# i2c_devices.net
KiCad netlist of a schematic drawn in Altium Designer
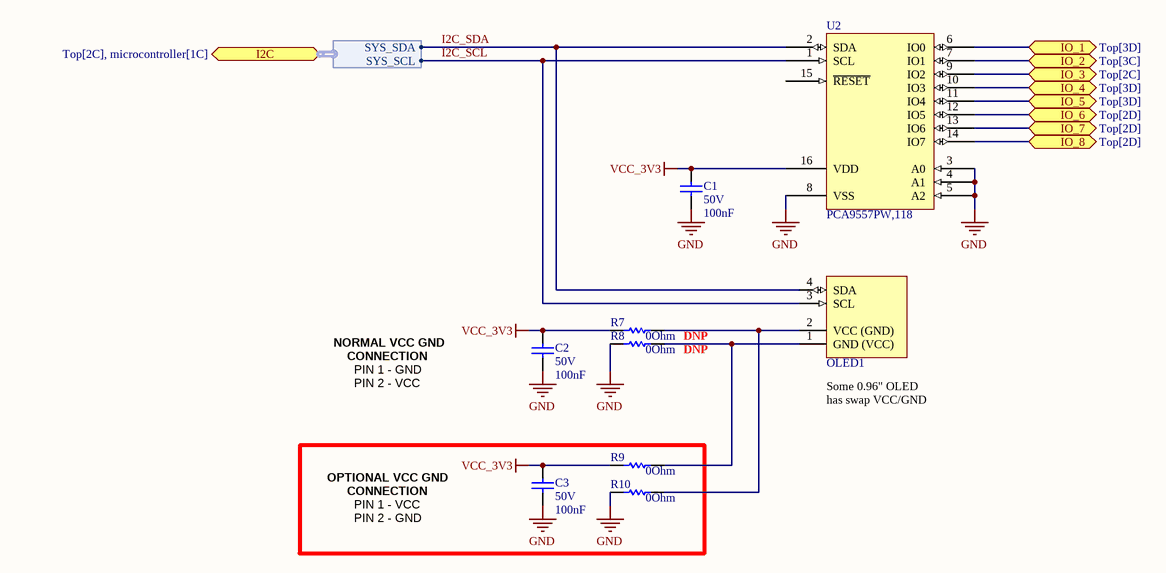
[diagram p0: i2c_devices.SchDoc]

(export (version "E")
  (design (tool "Eeschema 10.0.6"))
  (components
    (comp (ref "C1")
      (value "~")
      (footprint "CAP_0603_High_density")
      (description "Generic Ceramic Capacitor SMD")
      (fields
        (field (name "TOLERANCE") "10%")
        (field (name "VOLTAGE") "50V")
        (field (name "CAPACITANCE") "100nF")
      )
      (libsource (lib "altium_conclusive_library") (part "Capacitor SMD"))
    )
    (comp (ref "C2")
      (value "~")
      (footprint "CAP_0603_High_density")
      (description "Generic Ceramic Capacitor SMD")
      (fields
        (field (name "TOLERANCE") "10%")
        (field (name "VOLTAGE") "50V")
        (field (name "CAPACITANCE") "100nF")
      )
      (libsource (lib "altium_conclusive_library") (part "Capacitor SMD"))
    )
    (comp (ref "C3")
      (value "~")
      (footprint "CAP_0603_High_density")
      (description "Generic Ceramic Capacitor SMD")
      (fields
        (field (name "TOLERANCE") "10%")
        (field (name "VOLTAGE") "50V")
        (field (name "CAPACITANCE") "100nF")
      )
      (libsource (lib "altium_conclusive_library") (part "Capacitor SMD"))
    )
    (comp (ref "OLED1")
      (value "MDOB128064WV-YBI")
      (footprint "OLED_I2C")
      (description "Graphic OLED, 128 x 64 Pixels, Yellow on Black, 3.3V, I2C, 27.30mm x 27.30mm x 2.72mm panel size")
      (libsource (lib "altium_conclusive_library") (part "OLED_I2C"))
    )
    (comp (ref "R7")
      (value "RES_0_0402_1_1/16")
      (footprint "RES_0603")
      (description "Generic Resistor SMD")
      (fields (field (name "RESISTANCE") "0Ohm"))
      (libsource (lib "altium_conclusive_library") (part "Resistor SMD"))
    )
    (comp (ref "R8")
      (value "RES_0_0402_1_1/16")
      (footprint "RES_0603")
      (description "Generic Resistor SMD")
      (fields (field (name "RESISTANCE") "0Ohm"))
      (libsource (lib "altium_conclusive_library") (part "Resistor SMD"))
    )
    (comp (ref "R9")
      (value "RES_0_0402_1_1/16")
      (footprint "RES_0603")
      (description "Generic Resistor SMD")
      (fields (field (name "RESISTANCE") "0Ohm"))
      (libsource (lib "altium_conclusive_library") (part "Resistor SMD"))
    )
    (comp (ref "R10")
      (value "RES_0_0402_1_1/16")
      (footprint "RES_0603")
      (description "Generic Resistor SMD")
      (fields (field (name "RESISTANCE") "0Ohm"))
      (libsource (lib "altium_conclusive_library") (part "Resistor SMD"))
    )
    (comp (ref "U2")
      (value "PCA9557PW,118")
      (footprint "TSOP65P640X120-16M")
      (description "8-bit I2C-bus and SMBus I/O port with reset")
      (libsource (lib "MY_LIB") (part "PCA9557PW,118"))
    )
  )
  (nets
    (net (code "2") (name "/I2C_SCL") (class "Default")
      (node (ref "OLED1") (pin "3") (pinfunction "SCL_3") (pintype "input"))
      (node (ref "U2") (pin "1") (pinfunction "SCL_1") (pintype "input"))
    )
    (net (code "3") (name "/I2C_SDA") (class "Default")
      (node (ref "OLED1") (pin "4") (pinfunction "SDA_4") (pintype "bidirectional"))
      (node (ref "U2") (pin "2") (pinfunction "SDA_2") (pintype "bidirectional"))
    )
    (net (code "4") (name "/IO_1") (class "Default")
      (node (ref "U2") (pin "6") (pinfunction "IO0_6") (pintype "bidirectional"))
    )
    (net (code "5") (name "/IO_2") (class "Default")
      (node (ref "U2") (pin "7") (pinfunction "IO1_7") (pintype "bidirectional"))
    )
    (net (code "6") (name "/IO_3") (class "Default")
      (node (ref "U2") (pin "9") (pinfunction "IO2_9") (pintype "bidirectional"))
    )
    (net (code "7") (name "/IO_4") (class "Default")
      (node (ref "U2") (pin "10") (pinfunction "IO3_10") (pintype "bidirectional"))
    )
    (net (code "8") (name "/IO_5") (class "Default")
      (node (ref "U2") (pin "11") (pinfunction "IO4_11") (pintype "bidirectional"))
    )
    (net (code "9") (name "/IO_6") (class "Default")
      (node (ref "U2") (pin "12") (pinfunction "IO5_12") (pintype "bidirectional"))
    )
    (net (code "10") (name "/IO_7") (class "Default")
      (node (ref "U2") (pin "13") (pinfunction "IO6_13") (pintype "bidirectional"))
    )
    (net (code "11") (name "/IO_8") (class "Default")
      (node (ref "U2") (pin "14") (pinfunction "IO7_14") (pintype "bidirectional"))
    )
    (net (code "13") (name "GND") (class "Default")
      (node (ref "C1") (pin "2") (pinfunction "2_2") (pintype "passive"))
      (node (ref "C2") (pin "2") (pinfunction "2_2") (pintype "passive"))
      (node (ref "C3") (pin "2") (pinfunction "2_2") (pintype "passive"))
      (node (ref "R10") (pin "2") (pinfunction "2_2") (pintype "passive"))
      (node (ref "R8") (pin "2") (pinfunction "2_2") (pintype "passive"))
      (node (ref "U2") (pin "3") (pinfunction "A0_3") (pintype "input"))
      (node (ref "U2") (pin "4") (pinfunction "A1_4") (pintype "input"))
      (node (ref "U2") (pin "5") (pinfunction "A2_5") (pintype "input"))
      (node (ref "U2") (pin "8") (pinfunction "VSS_8") (pintype "power_in"))
    )
    (net (code "14") (name "Net-(OLED1-GND_(VCC))") (class "Default")
      (node (ref "OLED1") (pin "1") (pinfunction "GND_(VCC)_1") (pintype "passive"))
      (node (ref "R8") (pin "1") (pinfunction "1_1") (pintype "passive"))
      (node (ref "R9") (pin "1") (pinfunction "1_1") (pintype "passive"))
    )
    (net (code "15") (name "Net-(OLED1-VCC_(GND))") (class "Default")
      (node (ref "OLED1") (pin "2") (pinfunction "VCC_(GND)_2") (pintype "passive"))
      (node (ref "R10") (pin "1") (pinfunction "1_1") (pintype "passive"))
      (node (ref "R7") (pin "1") (pinfunction "1_1") (pintype "passive"))
    )
    (net (code "16") (name "VCC_3V3") (class "Default")
      (node (ref "C1") (pin "1") (pinfunction "1_1") (pintype "passive"))
      (node (ref "C2") (pin "1") (pinfunction "1_1") (pintype "passive"))
      (node (ref "C3") (pin "1") (pinfunction "1_1") (pintype "passive"))
      (node (ref "R7") (pin "2") (pinfunction "2_2") (pintype "passive"))
      (node (ref "R9") (pin "2") (pinfunction "2_2") (pintype "passive"))
      (node (ref "U2") (pin "16") (pinfunction "VDD_16") (pintype "power_in"))
    )
    (net (code "17") (name "unconnected-(U2-~{RESET}-Pad15)") (class "Default")
      (node (ref "U2") (pin "15") (pinfunction "~{RESET}_15") (pintype "input"))
    )
  )
)
